# obc-db.net
KiCad netlist of a schematic drawn in Altium Designer
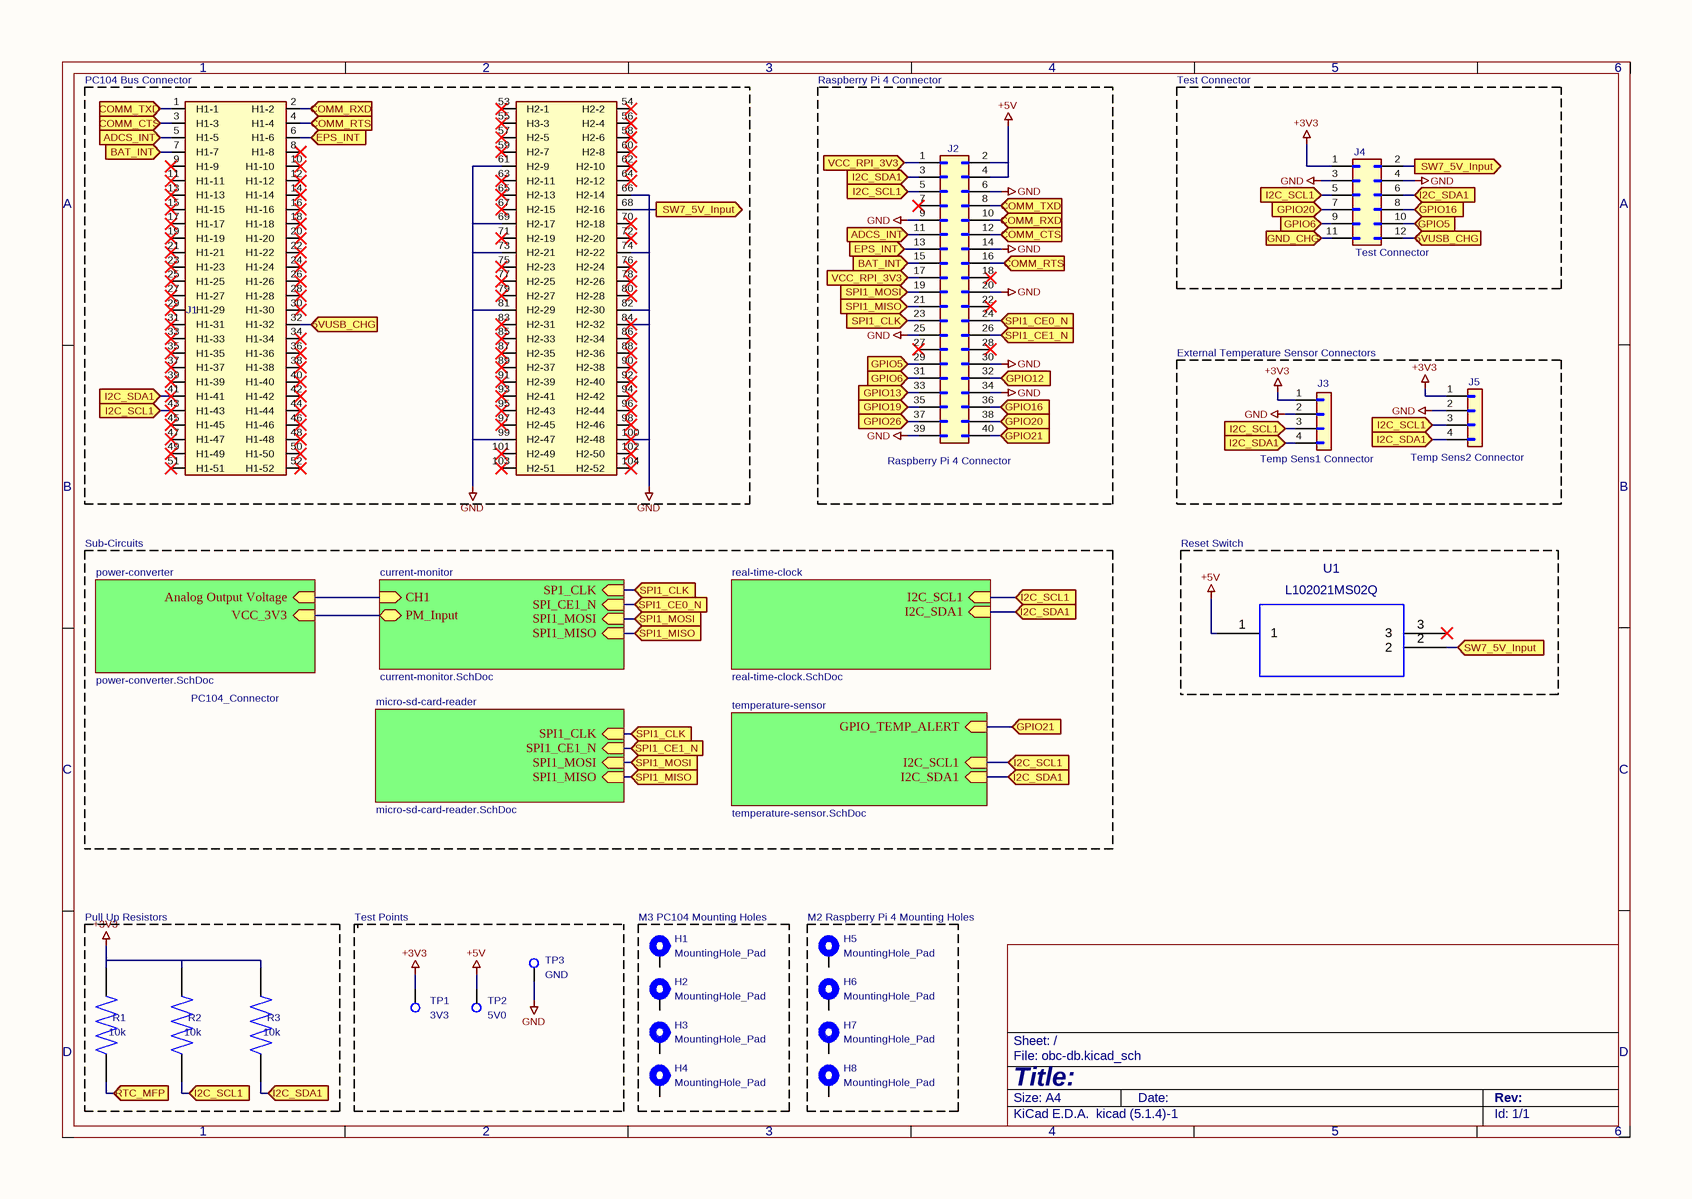
[diagram p0: obc-db.SchDoc]

(export (version "E")
  (design (tool "Eeschema 10.0.6"))
  (components
    (comp (ref "H1") (value "MountingHole_Pad") (libsource (lib "Mechanical") (part "MountingHole_Pad")))
    (comp (ref "H2") (value "MountingHole_Pad") (libsource (lib "Mechanical") (part "MountingHole_Pad")))
    (comp (ref "H3") (value "MountingHole_Pad") (libsource (lib "Mechanical") (part "MountingHole_Pad")))
    (comp (ref "H4") (value "MountingHole_Pad") (libsource (lib "Mechanical") (part "MountingHole_Pad")))
    (comp (ref "H5") (value "MountingHole_Pad") (libsource (lib "Mechanical") (part "MountingHole_Pad")))
    (comp (ref "H6") (value "MountingHole_Pad") (libsource (lib "Mechanical") (part "MountingHole_Pad")))
    (comp (ref "H7") (value "MountingHole_Pad") (libsource (lib "Mechanical") (part "MountingHole_Pad")))
    (comp (ref "H8") (value "MountingHole_Pad") (libsource (lib "Mechanical") (part "MountingHole_Pad")))
    (comp (ref "J1") (value "PC104_Connector") (libsource (lib "pc104-connector") (part "pc104-connector")))
    (comp (ref "J2")
      (value "Raspberry Pi 4 Connector")
      (libsource (lib "Connector_Generic") (part "Conn_02x20_Odd_Even"))
    )
    (comp (ref "J3") (value "Temp Sens1 Connector") (libsource (lib "Connector_Generic") (part "Conn_01x04")))
    (comp (ref "J4")
      (value "Test Connector")
      (libsource (lib "Connector_Generic") (part "Conn_02x06_Odd_Even"))
    )
    (comp (ref "J5") (value "Temp Sens2 Connector") (libsource (lib "Connector_Generic") (part "Conn_01x04")))
    (comp (ref "R1") (value "10k") (libsource (lib "ESR03EZPF1002") (part "ESR03EZPF1002")))
    (comp (ref "R2") (value "10k") (libsource (lib "ESR03EZPF1002") (part "ESR03EZPF1002")))
    (comp (ref "R3") (value "10k") (libsource (lib "ESR03EZPF1002") (part "ESR03EZPF1002")))
    (comp (ref "TP1") (value "3V3") (libsource (lib "Connector") (part "TestPoint")))
    (comp (ref "TP2") (value "5V0") (libsource (lib "Connector") (part "TestPoint")))
    (comp (ref "TP3") (value "GND") (libsource (lib "Connector") (part "TestPoint")))
    (comp (ref "U1") (value "L102021MS02Q") (libsource (lib "Daughterboard_Symbols") (part "L102021MS02Q")))
  )
  (nets
    (net (code "1") (name "+3V3") (class "Default")
      (node (ref "J3") (pin "1") (pinfunction "Pin_1_1") (pintype "passive"))
      (node (ref "J4") (pin "1") (pinfunction "Pin_1_1") (pintype "passive"))
      (node (ref "J5") (pin "1") (pinfunction "Pin_1_1") (pintype "passive"))
      (node (ref "R1") (pin "1") (pinfunction "1_1") (pintype "passive"))
      (node (ref "R2") (pin "1") (pinfunction "1_1") (pintype "passive"))
      (node (ref "R3") (pin "1") (pinfunction "1_1") (pintype "passive"))
      (node (ref "TP1") (pin "1") (pinfunction "1_1") (pintype "passive"))
    )
    (net (code "2") (name "+5V") (class "Default")
      (node (ref "J2") (pin "2") (pinfunction "Pin_2_2") (pintype "passive"))
      (node (ref "J2") (pin "4") (pinfunction "Pin_4_4") (pintype "passive"))
      (node (ref "TP2") (pin "1") (pinfunction "1_1") (pintype "passive"))
      (node (ref "U1") (pin "1") (pinfunction "1_1") (pintype "passive"))
    )
    (net (code "3") (name "/5VUSB_CHG") (class "Default")
      (node (ref "J1") (pin "32") (pinfunction "H1-32_32") (pintype "passive"))
      (node (ref "J4") (pin "12") (pinfunction "Pin_12_12") (pintype "passive"))
    )
    (net (code "4") (name "/ADCS_INT") (class "Default")
      (node (ref "J1") (pin "5") (pinfunction "H1-5_5") (pintype "passive"))
      (node (ref "J2") (pin "11") (pinfunction "Pin_11_11") (pintype "passive"))
    )
    (net (code "6") (name "/BAT_INT") (class "Default")
      (node (ref "J1") (pin "7") (pinfunction "H1-7_7") (pintype "passive"))
      (node (ref "J2") (pin "15") (pinfunction "Pin_15_15") (pintype "passive"))
    )
    (net (code "7") (name "/COMM_CTS") (class "Default")
      (node (ref "J1") (pin "3") (pinfunction "H1-3_3") (pintype "passive"))
      (node (ref "J2") (pin "12") (pinfunction "Pin_12_12") (pintype "passive"))
    )
    (net (code "8") (name "/COMM_RTS") (class "Default")
      (node (ref "J1") (pin "4") (pinfunction "H1-4_4") (pintype "passive"))
      (node (ref "J2") (pin "16") (pinfunction "Pin_16_16") (pintype "passive"))
    )
    (net (code "9") (name "/COMM_RXD") (class "Default")
      (node (ref "J1") (pin "2") (pinfunction "H1-2_2") (pintype "passive"))
      (node (ref "J2") (pin "10") (pinfunction "Pin_10_10") (pintype "passive"))
    )
    (net (code "10") (name "/COMM_TXD") (class "Default")
      (node (ref "J1") (pin "1") (pinfunction "H1-1_1") (pintype "passive"))
      (node (ref "J2") (pin "8") (pinfunction "Pin_8_8") (pintype "passive"))
    )
    (net (code "11") (name "/EPS_INT") (class "Default")
      (node (ref "J1") (pin "6") (pinfunction "H1-6_6") (pintype "passive"))
      (node (ref "J2") (pin "13") (pinfunction "Pin_13_13") (pintype "passive"))
    )
    (net (code "12") (name "/GND_CHG") (class "Default")
      (node (ref "J4") (pin "11") (pinfunction "Pin_11_11") (pintype "passive"))
    )
    (net (code "13") (name "/GPIO5") (class "Default")
      (node (ref "J2") (pin "29") (pinfunction "Pin_29_29") (pintype "passive"))
      (node (ref "J4") (pin "10") (pinfunction "Pin_10_10") (pintype "passive"))
    )
    (net (code "14") (name "/GPIO6") (class "Default")
      (node (ref "J2") (pin "31") (pinfunction "Pin_31_31") (pintype "passive"))
      (node (ref "J4") (pin "9") (pinfunction "Pin_9_9") (pintype "passive"))
    )
    (net (code "15") (name "/GPIO12") (class "Default")
      (node (ref "J2") (pin "32") (pinfunction "Pin_32_32") (pintype "passive"))
    )
    (net (code "16") (name "/GPIO13") (class "Default")
      (node (ref "J2") (pin "33") (pinfunction "Pin_33_33") (pintype "passive"))
    )
    (net (code "17") (name "/GPIO16") (class "Default")
      (node (ref "J2") (pin "36") (pinfunction "Pin_36_36") (pintype "passive"))
      (node (ref "J4") (pin "8") (pinfunction "Pin_8_8") (pintype "passive"))
    )
    (net (code "18") (name "/GPIO19") (class "Default")
      (node (ref "J2") (pin "35") (pinfunction "Pin_35_35") (pintype "passive"))
    )
    (net (code "19") (name "/GPIO20") (class "Default")
      (node (ref "J2") (pin "38") (pinfunction "Pin_38_38") (pintype "passive"))
      (node (ref "J4") (pin "7") (pinfunction "Pin_7_7") (pintype "passive"))
    )
    (net (code "20") (name "/GPIO21") (class "Default")
      (node (ref "J2") (pin "40") (pinfunction "Pin_40_40") (pintype "passive"))
    )
    (net (code "21") (name "/GPIO26") (class "Default")
      (node (ref "J2") (pin "37") (pinfunction "Pin_37_37") (pintype "passive"))
    )
    (net (code "22") (name "/I2C_SCL1") (class "Default")
      (node (ref "J1") (pin "43") (pinfunction "H1-43_43") (pintype "passive"))
      (node (ref "J2") (pin "5") (pinfunction "Pin_5_5") (pintype "passive"))
      (node (ref "J3") (pin "3") (pinfunction "Pin_3_3") (pintype "passive"))
      (node (ref "J4") (pin "5") (pinfunction "Pin_5_5") (pintype "passive"))
      (node (ref "J5") (pin "3") (pinfunction "Pin_3_3") (pintype "passive"))
      (node (ref "R2") (pin "2") (pinfunction "2_2") (pintype "passive"))
    )
    (net (code "23") (name "/I2C_SDA1") (class "Default")
      (node (ref "J1") (pin "41") (pinfunction "H1-41_41") (pintype "passive"))
      (node (ref "J2") (pin "3") (pinfunction "Pin_3_3") (pintype "passive"))
      (node (ref "J3") (pin "4") (pinfunction "Pin_4_4") (pintype "passive"))
      (node (ref "J4") (pin "6") (pinfunction "Pin_6_6") (pintype "passive"))
      (node (ref "J5") (pin "4") (pinfunction "Pin_4_4") (pintype "passive"))
      (node (ref "R3") (pin "2") (pinfunction "2_2") (pintype "passive"))
    )
    (net (code "25") (name "/RTC_MFP") (class "Default")
      (node (ref "R1") (pin "2") (pinfunction "2_2") (pintype "passive"))
    )
    (net (code "26") (name "/SPI1_CE0_N") (class "Default")
      (node (ref "J2") (pin "24") (pinfunction "Pin_24_24") (pintype "passive"))
    )
    (net (code "27") (name "/SPI1_CE1_N") (class "Default")
      (node (ref "J2") (pin "26") (pinfunction "Pin_26_26") (pintype "passive"))
    )
    (net (code "28") (name "/SPI1_CLK") (class "Default")
      (node (ref "J2") (pin "23") (pinfunction "Pin_23_23") (pintype "passive"))
    )
    (net (code "29") (name "/SPI1_MISO") (class "Default")
      (node (ref "J2") (pin "21") (pinfunction "Pin_21_21") (pintype "passive"))
    )
    (net (code "30") (name "/SPI1_MOSI") (class "Default")
      (node (ref "J2") (pin "19") (pinfunction "Pin_19_19") (pintype "passive"))
    )
    (net (code "31") (name "/SW7_5V_Input") (class "Default")
      (node (ref "J1") (pin "68") (pinfunction "H2-16_68") (pintype "passive"))
      (node (ref "J4") (pin "2") (pinfunction "Pin_2_2") (pintype "passive"))
      (node (ref "U1") (pin "2") (pinfunction "2_2") (pintype "passive"))
    )
    (net (code "32") (name "/VCC_RPI_3V3") (class "Default")
      (node (ref "J2") (pin "1") (pinfunction "Pin_1_1") (pintype "passive"))
      (node (ref "J2") (pin "17") (pinfunction "Pin_17_17") (pintype "passive"))
    )
    (net (code "33") (name "GND") (class "Default")
      (node (ref "J1") (pin "100") (pinfunction "H2-48_100") (pintype "passive"))
      (node (ref "J1") (pin "61") (pinfunction "H2-9_61") (pintype "passive"))
      (node (ref "J1") (pin "66") (pinfunction "H2-14_66") (pintype "passive"))
      (node (ref "J1") (pin "69") (pinfunction "H2-17_69") (pintype "passive"))
      (node (ref "J1") (pin "73") (pinfunction "H2-21_73") (pintype "passive"))
      (node (ref "J1") (pin "74") (pinfunction "H2-22_74") (pintype "passive"))
      (node (ref "J1") (pin "81") (pinfunction "H2-29_81") (pintype "passive"))
      (node (ref "J1") (pin "82") (pinfunction "H2-30_82") (pintype "passive"))
      (node (ref "J1") (pin "84") (pinfunction "H2-32_84") (pintype "passive"))
      (node (ref "J1") (pin "99") (pinfunction "H2-47_99") (pintype "passive"))
      (node (ref "J2") (pin "14") (pinfunction "Pin_14_14") (pintype "passive"))
      (node (ref "J2") (pin "20") (pinfunction "Pin_20_20") (pintype "passive"))
      (node (ref "J2") (pin "25") (pinfunction "Pin_25_25") (pintype "passive"))
      (node (ref "J2") (pin "30") (pinfunction "Pin_30_30") (pintype "passive"))
      (node (ref "J2") (pin "34") (pinfunction "Pin_34_34") (pintype "passive"))
      (node (ref "J2") (pin "39") (pinfunction "Pin_39_39") (pintype "passive"))
      (node (ref "J2") (pin "6") (pinfunction "Pin_6_6") (pintype "passive"))
      (node (ref "J2") (pin "9") (pinfunction "Pin_9_9") (pintype "passive"))
      (node (ref "J3") (pin "2") (pinfunction "Pin_2_2") (pintype "passive"))
      (node (ref "J4") (pin "3") (pinfunction "Pin_3_3") (pintype "passive"))
      (node (ref "J4") (pin "4") (pinfunction "Pin_4_4") (pintype "passive"))
      (node (ref "J5") (pin "2") (pinfunction "Pin_2_2") (pintype "passive"))
      (node (ref "TP3") (pin "1") (pinfunction "1_1") (pintype "passive"))
    )
    (net (code "34") (name "unconnected-(H1-Pad1)") (class "Default")
      (node (ref "H1") (pin "1") (pinfunction "1_1") (pintype "passive"))
    )
    (net (code "35") (name "unconnected-(H2-Pad1)") (class "Default")
      (node (ref "H2") (pin "1") (pinfunction "1_1") (pintype "passive"))
    )
    (net (code "36") (name "unconnected-(H3-Pad1)") (class "Default")
      (node (ref "H3") (pin "1") (pinfunction "1_1") (pintype "passive"))
    )
    (net (code "37") (name "unconnected-(H4-Pad1)") (class "Default")
      (node (ref "H4") (pin "1") (pinfunction "1_1") (pintype "passive"))
    )
    (net (code "38") (name "unconnected-(H5-Pad1)") (class "Default")
      (node (ref "H5") (pin "1") (pinfunction "1_1") (pintype "passive"))
    )
    (net (code "39") (name "unconnected-(H6-Pad1)") (class "Default")
      (node (ref "H6") (pin "1") (pinfunction "1_1") (pintype "passive"))
    )
    (net (code "40") (name "unconnected-(H7-Pad1)") (class "Default")
      (node (ref "H7") (pin "1") (pinfunction "1_1") (pintype "passive"))
    )
    (net (code "41") (name "unconnected-(H8-Pad1)") (class "Default")
      (node (ref "H8") (pin "1") (pinfunction "1_1") (pintype "passive"))
    )
    (net (code "42") (name "unconnected-(J1-H1-8-Pad8)") (class "Default")
      (node (ref "J1") (pin "8") (pinfunction "H1-8_8") (pintype "passive+no_connect"))
    )
    (net (code "43") (name "unconnected-(J1-H1-9-Pad9)") (class "Default")
      (node (ref "J1") (pin "9") (pinfunction "H1-9_9") (pintype "passive+no_connect"))
    )
    (net (code "44") (name "unconnected-(J1-H1-10-Pad10)") (class "Default")
      (node (ref "J1") (pin "10") (pinfunction "H1-10_10") (pintype "passive+no_connect"))
    )
    (net (code "45") (name "unconnected-(J1-H1-11-Pad11)") (class "Default")
      (node (ref "J1") (pin "11") (pinfunction "H1-11_11") (pintype "passive+no_connect"))
    )
    (net (code "46") (name "unconnected-(J1-H1-12-Pad12)") (class "Default")
      (node (ref "J1") (pin "12") (pinfunction "H1-12_12") (pintype "passive+no_connect"))
    )
    (net (code "47") (name "unconnected-(J1-H1-13-Pad13)") (class "Default")
      (node (ref "J1") (pin "13") (pinfunction "H1-13_13") (pintype "passive+no_connect"))
    )
    (net (code "48") (name "unconnected-(J1-H1-14-Pad14)") (class "Default")
      (node (ref "J1") (pin "14") (pinfunction "H1-14_14") (pintype "passive+no_connect"))
    )
    (net (code "49") (name "unconnected-(J1-H1-15-Pad15)") (class "Default")
      (node (ref "J1") (pin "15") (pinfunction "H1-15_15") (pintype "passive+no_connect"))
    )
    (net (code "50") (name "unconnected-(J1-H1-16-Pad16)") (class "Default")
      (node (ref "J1") (pin "16") (pinfunction "H1-16_16") (pintype "passive+no_connect"))
    )
    (net (code "51") (name "unconnected-(J1-H1-17-Pad17)") (class "Default")
      (node (ref "J1") (pin "17") (pinfunction "H1-17_17") (pintype "passive+no_connect"))
    )
    (net (code "52") (name "unconnected-(J1-H1-18-Pad18)") (class "Default")
      (node (ref "J1") (pin "18") (pinfunction "H1-18_18") (pintype "passive+no_connect"))
    )
    (net (code "53") (name "unconnected-(J1-H1-19-Pad19)") (class "Default")
      (node (ref "J1") (pin "19") (pinfunction "H1-19_19") (pintype "passive+no_connect"))
    )
    (net (code "54") (name "unconnected-(J1-H1-20-Pad20)") (class "Default")
      (node (ref "J1") (pin "20") (pinfunction "H1-20_20") (pintype "passive+no_connect"))
    )
    (net (code "55") (name "unconnected-(J1-H1-21-Pad21)") (class "Default")
      (node (ref "J1") (pin "21") (pinfunction "H1-21_21") (pintype "passive+no_connect"))
    )
    (net (code "56") (name "unconnected-(J1-H1-22-Pad22)") (class "Default")
      (node (ref "J1") (pin "22") (pinfunction "H1-22_22") (pintype "passive+no_connect"))
    )
    (net (code "57") (name "unconnected-(J1-H1-23-Pad23)") (class "Default")
      (node (ref "J1") (pin "23") (pinfunction "H1-23_23") (pintype "passive+no_connect"))
    )
    (net (code "58") (name "unconnected-(J1-H1-24-Pad24)") (class "Default")
      (node (ref "J1") (pin "24") (pinfunction "H1-24_24") (pintype "passive+no_connect"))
    )
    (net (code "59") (name "unconnected-(J1-H1-25-Pad25)") (class "Default")
      (node (ref "J1") (pin "25") (pinfunction "H1-25_25") (pintype "passive+no_connect"))
    )
    (net (code "60") (name "unconnected-(J1-H1-26-Pad26)") (class "Default")
      (node (ref "J1") (pin "26") (pinfunction "H1-26_26") (pintype "passive+no_connect"))
    )
    (net (code "61") (name "unconnected-(J1-H1-27-Pad27)") (class "Default")
      (node (ref "J1") (pin "27") (pinfunction "H1-27_27") (pintype "passive+no_connect"))
    )
    (net (code "62") (name "unconnected-(J1-H1-28-Pad28)") (class "Default")
      (node (ref "J1") (pin "28") (pinfunction "H1-28_28") (pintype "passive+no_connect"))
    )
    (net (code "63") (name "unconnected-(J1-H1-29-Pad29)") (class "Default")
      (node (ref "J1") (pin "29") (pinfunction "H1-29_29") (pintype "passive+no_connect"))
    )
    (net (code "64") (name "unconnected-(J1-H1-30-Pad30)") (class "Default")
      (node (ref "J1") (pin "30") (pinfunction "H1-30_30") (pintype "passive+no_connect"))
    )
    (net (code "65") (name "unconnected-(J1-H1-31-Pad31)") (class "Default")
      (node (ref "J1") (pin "31") (pinfunction "H1-31_31") (pintype "passive+no_connect"))
    )
    (net (code "66") (name "unconnected-(J1-H1-33-Pad33)") (class "Default")
      (node (ref "J1") (pin "33") (pinfunction "H1-33_33") (pintype "passive+no_connect"))
    )
    (net (code "67") (name "unconnected-(J1-H1-34-Pad34)") (class "Default")
      (node (ref "J1") (pin "34") (pinfunction "H1-34_34") (pintype "passive+no_connect"))
    )
    (net (code "68") (name "unconnected-(J1-H1-35-Pad35)") (class "Default")
      (node (ref "J1") (pin "35") (pinfunction "H1-35_35") (pintype "passive+no_connect"))
    )
    (net (code "69") (name "unconnected-(J1-H1-36-Pad36)") (class "Default")
      (node (ref "J1") (pin "36") (pinfunction "H1-36_36") (pintype "passive+no_connect"))
    )
    (net (code "70") (name "unconnected-(J1-H1-37-Pad37)") (class "Default")
      (node (ref "J1") (pin "37") (pinfunction "H1-37_37") (pintype "passive+no_connect"))
    )
    (net (code "71") (name "unconnected-(J1-H1-38-Pad38)") (class "Default")
      (node (ref "J1") (pin "38") (pinfunction "H1-38_38") (pintype "passive+no_connect"))
    )
    (net (code "72") (name "unconnected-(J1-H1-39-Pad39)") (class "Default")
      (node (ref "J1") (pin "39") (pinfunction "H1-39_39") (pintype "passive+no_connect"))
    )
    (net (code "73") (name "unconnected-(J1-H1-40-Pad40)") (class "Default")
      (node (ref "J1") (pin "40") (pinfunction "H1-40_40") (pintype "passive+no_connect"))
    )
    (net (code "74") (name "unconnected-(J1-H1-42-Pad42)") (class "Default")
      (node (ref "J1") (pin "42") (pinfunction "H1-42_42") (pintype "passive+no_connect"))
    )
    (net (code "75") (name "unconnected-(J1-H1-44-Pad44)") (class "Default")
      (node (ref "J1") (pin "44") (pinfunction "H1-44_44") (pintype "passive+no_connect"))
    )
    (net (code "76") (name "unconnected-(J1-H1-45-Pad45)") (class "Default")
      (node (ref "J1") (pin "45") (pinfunction "H1-45_45") (pintype "passive+no_connect"))
    )
    (net (code "77") (name "unconnected-(J1-H1-46-Pad46)") (class "Default")
      (node (ref "J1") (pin "46") (pinfunction "H1-46_46") (pintype "passive+no_connect"))
    )
    (net (code "78") (name "unconnected-(J1-H1-47-Pad47)") (class "Default")
      (node (ref "J1") (pin "47") (pinfunction "H1-47_47") (pintype "passive+no_connect"))
    )
    (net (code "79") (name "unconnected-(J1-H1-48-Pad48)") (class "Default")
      (node (ref "J1") (pin "48") (pinfunction "H1-48_48") (pintype "passive+no_connect"))
    )
    (net (code "80") (name "unconnected-(J1-H1-49-Pad49)") (class "Default")
      (node (ref "J1") (pin "49") (pinfunction "H1-49_49") (pintype "passive+no_connect"))
    )
    (net (code "81") (name "unconnected-(J1-H1-50-Pad50)") (class "Default")
      (node (ref "J1") (pin "50") (pinfunction "H1-50_50") (pintype "passive+no_connect"))
    )
    (net (code "82") (name "unconnected-(J1-H1-51-Pad51)") (class "Default")
      (node (ref "J1") (pin "51") (pinfunction "H1-51_51") (pintype "passive+no_connect"))
    )
    (net (code "83") (name "unconnected-(J1-H1-52-Pad52)") (class "Default")
      (node (ref "J1") (pin "52") (pinfunction "H1-52_52") (pintype "passive+no_connect"))
    )
    (net (code "84") (name "unconnected-(J1-H2-1-Pad53)") (class "Default")
      (node (ref "J1") (pin "53") (pinfunction "H2-1_53") (pintype "passive+no_connect"))
    )
    (net (code "85") (name "unconnected-(J1-H2-2-Pad54)") (class "Default")
      (node (ref "J1") (pin "54") (pinfunction "H2-2_54") (pintype "passive+no_connect"))
    )
    (net (code "86") (name "unconnected-(J1-H2-4-Pad56)") (class "Default")
      (node (ref "J1") (pin "56") (pinfunction "H2-4_56") (pintype "passive+no_connect"))
    )
    (net (code "87") (name "unconnected-(J1-H2-5-Pad57)") (class "Default")
      (node (ref "J1") (pin "57") (pinfunction "H2-5_57") (pintype "passive+no_connect"))
    )
    (net (code "88") (name "unconnected-(J1-H2-6-Pad58)") (class "Default")
      (node (ref "J1") (pin "58") (pinfunction "H2-6_58") (pintype "passive+no_connect"))
    )
    (net (code "89") (name "unconnected-(J1-H2-7-Pad59)") (class "Default")
      (node (ref "J1") (pin "59") (pinfunction "H2-7_59") (pintype "passive+no_connect"))
    )
    (net (code "90") (name "unconnected-(J1-H2-8-Pad60)") (class "Default")
      (node (ref "J1") (pin "60") (pinfunction "H2-8_60") (pintype "passive+no_connect"))
    )
    (net (code "91") (name "unconnected-(J1-H2-10-Pad62)") (class "Default")
      (node (ref "J1") (pin "62") (pinfunction "H2-10_62") (pintype "passive+no_connect"))
    )
    (net (code "92") (name "unconnected-(J1-H2-11-Pad63)") (class "Default")
      (node (ref "J1") (pin "63") (pinfunction "H2-11_63") (pintype "passive+no_connect"))
    )
    (net (code "93") (name "unconnected-(J1-H2-12-Pad64)") (class "Default")
      (node (ref "J1") (pin "64") (pinfunction "H2-12_64") (pintype "passive+no_connect"))
    )
    (net (code "94") (name "unconnected-(J1-H2-13-Pad65)") (class "Default")
      (node (ref "J1") (pin "65") (pinfunction "H2-13_65") (pintype "passive+no_connect"))
    )
    (net (code "95") (name "unconnected-(J1-H2-15-Pad67)") (class "Default")
      (node (ref "J1") (pin "67") (pinfunction "H2-15_67") (pintype "passive+no_connect"))
    )
    (net (code "96") (name "unconnected-(J1-H2-18-Pad70)") (class "Default")
      (node (ref "J1") (pin "70") (pinfunction "H2-18_70") (pintype "passive+no_connect"))
    )
    (net (code "97") (name "unconnected-(J1-H2-19-Pad71)") (class "Default")
      (node (ref "J1") (pin "71") (pinfunction "H2-19_71") (pintype "passive+no_connect"))
    )
    (net (code "98") (name "unconnected-(J1-H2-20-Pad72)") (class "Default")
      (node (ref "J1") (pin "72") (pinfunction "H2-20_72") (pintype "passive+no_connect"))
    )
    (net (code "99") (name "unconnected-(J1-H2-23-Pad75)") (class "Default")
      (node (ref "J1") (pin "75") (pinfunction "H2-23_75") (pintype "passive+no_connect"))
    )
    (net (code "100") (name "unconnected-(J1-H2-24-Pad76)") (class "Default")
      (node (ref "J1") (pin "76") (pinfunction "H2-24_76") (pintype "passive+no_connect"))
    )
    (net (code "101") (name "unconnected-(J1-H2-25-Pad77)") (class "Default")
      (node (ref "J1") (pin "77") (pinfunction "H2-25_77") (pintype "passive+no_connect"))
    )
    (net (code "102") (name "unconnected-(J1-H2-26-Pad78)") (class "Default")
      (node (ref "J1") (pin "78") (pinfunction "H2-26_78") (pintype "passive+no_connect"))
    )
    (net (code "103") (name "unconnected-(J1-H2-27-Pad79)") (class "Default")
      (node (ref "J1") (pin "79") (pinfunction "H2-27_79") (pintype "passive+no_connect"))
    )
    (net (code "104") (name "unconnected-(J1-H2-28-Pad80)") (class "Default")
      (node (ref "J1") (pin "80") (pinfunction "H2-28_80") (pintype "passive+no_connect"))
    )
    (net (code "105") (name "unconnected-(J1-H2-31-Pad83)") (class "Default")
      (node (ref "J1") (pin "83") (pinfunction "H2-31_83") (pintype "passive+no_connect"))
    )
    (net (code "106") (name "unconnected-(J1-H2-33-Pad85)") (class "Default")
      (node (ref "J1") (pin "85") (pinfunction "H2-33_85") (pintype "passive+no_connect"))
    )
    (net (code "107") (name "unconnected-(J1-H2-34-Pad86)") (class "Default")
      (node (ref "J1") (pin "86") (pinfunction "H2-34_86") (pintype "passive+no_connect"))
    )
    (net (code "108") (name "unconnected-(J1-H2-35-Pad87)") (class "Default")
      (node (ref "J1") (pin "87") (pinfunction "H2-35_87") (pintype "passive+no_connect"))
    )
    (net (code "109") (name "unconnected-(J1-H2-36-Pad88)") (class "Default")
      (node (ref "J1") (pin "88") (pinfunction "H2-36_88") (pintype "passive+no_connect"))
    )
    (net (code "110") (name "unconnected-(J1-H2-37-Pad89)") (class "Default")
      (node (ref "J1") (pin "89") (pinfunction "H2-37_89") (pintype "passive+no_connect"))
    )
    (net (code "111") (name "unconnected-(J1-H2-38-Pad90)") (class "Default")
      (node (ref "J1") (pin "90") (pinfunction "H2-38_90") (pintype "passive+no_connect"))
    )
    (net (code "112") (name "unconnected-(J1-H2-39-Pad91)") (class "Default")
      (node (ref "J1") (pin "91") (pinfunction "H2-39_91") (pintype "passive+no_connect"))
    )
    (net (code "113") (name "unconnected-(J1-H2-40-Pad92)") (class "Default")
      (node (ref "J1") (pin "92") (pinfunction "H2-40_92") (pintype "passive+no_connect"))
    )
    (net (code "114") (name "unconnected-(J1-H2-41-Pad93)") (class "Default")
      (node (ref "J1") (pin "93") (pinfunction "H2-41_93") (pintype "passive+no_connect"))
    )
    (net (code "115") (name "unconnected-(J1-H2-42-Pad94)") (class "Default")
      (node (ref "J1") (pin "94") (pinfunction "H2-42_94") (pintype "passive+no_connect"))
    )
    (net (code "116") (name "unconnected-(J1-H2-43-Pad95)") (class "Default")
      (node (ref "J1") (pin "95") (pinfunction "H2-43_95") (pintype "passive+no_connect"))
    )
    (net (code "117") (name "unconnected-(J1-H2-44-Pad96)") (class "Default")
      (node (ref "J1") (pin "96") (pinfunction "H2-44_96") (pintype "passive+no_connect"))
    )
    (net (code "118") (name "unconnected-(J1-H2-45-Pad97)") (class "Default")
      (node (ref "J1") (pin "97") (pinfunction "H2-45_97") (pintype "passive+no_connect"))
    )
    (net (code "119") (name "unconnected-(J1-H2-46-Pad98)") (class "Default")
      (node (ref "J1") (pin "98") (pinfunction "H2-46_98") (pintype "passive+no_connect"))
    )
    (net (code "120") (name "unconnected-(J1-H2-49-Pad101)") (class "Default")
      (node (ref "J1") (pin "101") (pinfunction "H2-49_101") (pintype "passive+no_connect"))
    )
    (net (code "121") (name "unconnected-(J1-H2-50-Pad102)") (class "Default")
      (node (ref "J1") (pin "102") (pinfunction "H2-50_102") (pintype "passive+no_connect"))
    )
    (net (code "122") (name "unconnected-(J1-H2-51-Pad103)") (class "Default")
      (node (ref "J1") (pin "103") (pinfunction "H2-51_103") (pintype "passive+no_connect"))
    )
    (net (code "123") (name "unconnected-(J1-H2-52-Pad104)") (class "Default")
      (node (ref "J1") (pin "104") (pinfunction "H2-52_104") (pintype "passive+no_connect"))
    )
    (net (code "124") (name "unconnected-(J1-H3-3-Pad55)") (class "Default")
      (node (ref "J1") (pin "55") (pinfunction "H3-3_55") (pintype "passive+no_connect"))
    )
    (net (code "125") (name "unconnected-(J2-Pin_7-Pad7)") (class "Default")
      (node (ref "J2") (pin "7") (pinfunction "Pin_7_7") (pintype "passive+no_connect"))
    )
    (net (code "126") (name "unconnected-(J2-Pin_18-Pad18)") (class "Default")
      (node (ref "J2") (pin "18") (pinfunction "Pin_18_18") (pintype "passive+no_connect"))
    )
    (net (code "127") (name "unconnected-(J2-Pin_22-Pad22)") (class "Default")
      (node (ref "J2") (pin "22") (pinfunction "Pin_22_22") (pintype "passive+no_connect"))
    )
    (net (code "128") (name "unconnected-(J2-Pin_27-Pad27)") (class "Default")
      (node (ref "J2") (pin "27") (pinfunction "Pin_27_27") (pintype "passive+no_connect"))
    )
    (net (code "129") (name "unconnected-(J2-Pin_28-Pad28)") (class "Default")
      (node (ref "J2") (pin "28") (pinfunction "Pin_28_28") (pintype "passive+no_connect"))
    )
    (net (code "130") (name "unconnected-(U1-Pad3)") (class "Default")
      (node (ref "U1") (pin "3") (pinfunction "3_3") (pintype "passive+no_connect"))
    )
  )
)
